# wooden_alarm.net
KiCad netlist of a schematic drawn in EAGLE
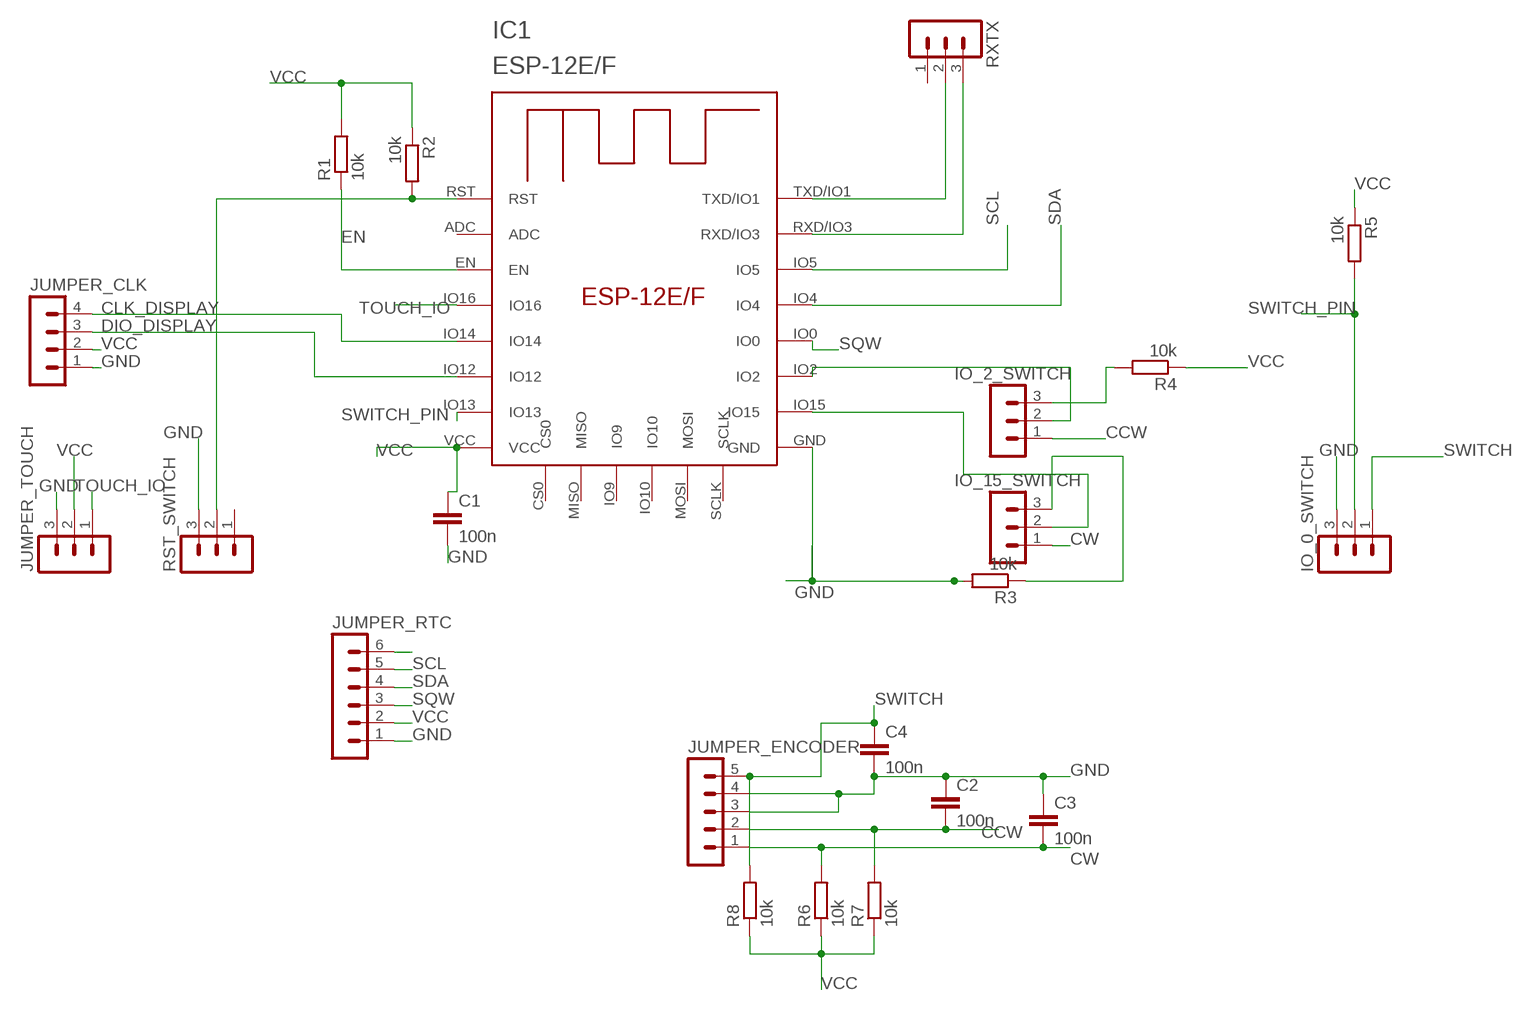
[diagram p0: schematic, sheet 1]

(export (version "E")
  (design (tool "Eeschema 10.0.6"))
  (components
    (comp (ref "C1")
      (value "100n")
      (footprint "eagle-import:C0805")
      (libsource (lib "eagle-import") (part "C-EUC0805"))
    )
    (comp (ref "C2")
      (value "100n")
      (footprint "eagle-import:C1206")
      (libsource (lib "eagle-import") (part "C-EUC1206"))
    )
    (comp (ref "C3")
      (value "100n")
      (footprint "eagle-import:C1206")
      (libsource (lib "eagle-import") (part "C-EUC1206"))
    )
    (comp (ref "C4")
      (value "100n")
      (footprint "eagle-import:C1206")
      (libsource (lib "eagle-import") (part "C-EUC1206"))
    )
    (comp (ref "IC1")
      (value "ESP-12E/F")
      (footprint "eagle-import:ESP-12E")
      (libsource (lib "eagle-import") (part "ESP-12E/F"))
    )
    (comp (ref "IO_0_SWITCH")
      (value "MA03-1")
      (footprint "eagle-import:MA03-1")
      (libsource (lib "eagle-import") (part "MA03-1"))
    )
    (comp (ref "IO_2_SWITCH")
      (value "MA03-1")
      (footprint "eagle-import:MA03-1")
      (libsource (lib "eagle-import") (part "MA03-1"))
    )
    (comp (ref "IO_15_SWITCH")
      (value "MA03-1")
      (footprint "eagle-import:MA03-1")
      (libsource (lib "eagle-import") (part "MA03-1"))
    )
    (comp (ref "JUMPER_CLK")
      (value "MA04-1")
      (footprint "eagle-import:MA04-1")
      (libsource (lib "eagle-import") (part "MA04-1"))
    )
    (comp (ref "JUMPER_ENCODER")
      (value "MA05-1")
      (footprint "eagle-import:MA05-1")
      (libsource (lib "eagle-import") (part "MA05-1"))
    )
    (comp (ref "JUMPER_RTC")
      (value "MA06-1")
      (footprint "eagle-import:MA06-1")
      (libsource (lib "eagle-import") (part "MA06-1"))
    )
    (comp (ref "JUMPER_TOUCH")
      (value "MA03-1")
      (footprint "eagle-import:MA03-1")
      (libsource (lib "eagle-import") (part "MA03-1"))
    )
    (comp (ref "R1")
      (value "10k")
      (footprint "eagle-import:R0805")
      (libsource (lib "eagle-import") (part "R-EU_R0805"))
    )
    (comp (ref "R2")
      (value "10k")
      (footprint "eagle-import:R0805")
      (libsource (lib "eagle-import") (part "R-EU_R0805"))
    )
    (comp (ref "R3")
      (value "10k")
      (footprint "eagle-import:R0805")
      (libsource (lib "eagle-import") (part "R-EU_R0805"))
    )
    (comp (ref "R4")
      (value "10k")
      (footprint "eagle-import:R0805")
      (libsource (lib "eagle-import") (part "R-EU_R0805"))
    )
    (comp (ref "R5")
      (value "10k")
      (footprint "eagle-import:R0805")
      (libsource (lib "eagle-import") (part "R-EU_R0805"))
    )
    (comp (ref "R6")
      (value "10k")
      (footprint "eagle-import:R0805")
      (libsource (lib "eagle-import") (part "R-EU_R0805"))
    )
    (comp (ref "R7")
      (value "10k")
      (footprint "eagle-import:R0805")
      (libsource (lib "eagle-import") (part "R-EU_R0805"))
    )
    (comp (ref "R8")
      (value "10k")
      (footprint "eagle-import:R0805")
      (libsource (lib "eagle-import") (part "R-EU_R0805"))
    )
    (comp (ref "RST_SWITCH")
      (value "MA03-1")
      (footprint "eagle-import:MA03-1")
      (libsource (lib "eagle-import") (part "MA03-1"))
    )
    (comp (ref "RXTX")
      (value "MA03-1")
      (footprint "eagle-import:MA03-1")
      (libsource (lib "eagle-import") (part "MA03-1"))
    )
  )
  (nets
    (net (code "1") (name "/CCW") (class "Default")
      (node (ref "C2") (pin "2") (pinfunction "2_2") (pintype "passive"))
      (node (ref "IO_2_SWITCH") (pin "1") (pinfunction "1_1") (pintype "passive"))
      (node (ref "JUMPER_ENCODER") (pin "2") (pinfunction "2_2") (pintype "passive"))
      (node (ref "R7") (pin "2") (pinfunction "2_2") (pintype "passive"))
    )
    (net (code "2") (name "/CLK_DISPLAY") (class "Default")
      (node (ref "IC1") (pin "IO14") (pinfunction "IO14_IO14") (pintype "bidirectional"))
      (node (ref "JUMPER_CLK") (pin "4") (pinfunction "4_4") (pintype "passive"))
    )
    (net (code "3") (name "/CW") (class "Default")
      (node (ref "C3") (pin "2") (pinfunction "2_2") (pintype "passive"))
      (node (ref "IO_15_SWITCH") (pin "1") (pinfunction "1_1") (pintype "passive"))
      (node (ref "JUMPER_ENCODER") (pin "1") (pinfunction "1_1") (pintype "passive"))
      (node (ref "R6") (pin "2") (pinfunction "2_2") (pintype "passive"))
    )
    (net (code "4") (name "/DIO_DISPLAY") (class "Default")
      (node (ref "IC1") (pin "IO12") (pinfunction "IO12_IO12") (pintype "bidirectional"))
      (node (ref "JUMPER_CLK") (pin "3") (pinfunction "3_3") (pintype "passive"))
    )
    (net (code "5") (name "/EN") (class "Default")
      (node (ref "IC1") (pin "EN") (pinfunction "EN_EN") (pintype "bidirectional"))
      (node (ref "R1") (pin "1") (pinfunction "1_1") (pintype "passive"))
    )
    (net (code "6") (name "/GND") (class "Default")
      (node (ref "C1") (pin "2") (pinfunction "2_2") (pintype "passive"))
      (node (ref "C2") (pin "1") (pinfunction "1_1") (pintype "passive"))
      (node (ref "C3") (pin "1") (pinfunction "1_1") (pintype "passive"))
      (node (ref "C4") (pin "2") (pinfunction "2_2") (pintype "passive"))
      (node (ref "IC1") (pin "GND") (pinfunction "GND_GND") (pintype "power_in"))
      (node (ref "IO_0_SWITCH") (pin "3") (pinfunction "3_3") (pintype "passive"))
      (node (ref "JUMPER_CLK") (pin "1") (pinfunction "1_1") (pintype "passive"))
      (node (ref "JUMPER_ENCODER") (pin "3") (pinfunction "3_3") (pintype "passive"))
      (node (ref "JUMPER_ENCODER") (pin "4") (pinfunction "4_4") (pintype "passive"))
      (node (ref "JUMPER_RTC") (pin "1") (pinfunction "1_1") (pintype "passive"))
      (node (ref "JUMPER_TOUCH") (pin "3") (pinfunction "3_3") (pintype "passive"))
      (node (ref "R3") (pin "2") (pinfunction "2_2") (pintype "passive"))
      (node (ref "RST_SWITCH") (pin "3") (pinfunction "3_3") (pintype "passive"))
    )
    (net (code "7") (name "/SCL") (class "Default")
      (node (ref "IC1") (pin "IO5") (pinfunction "IO5_IO5") (pintype "bidirectional"))
      (node (ref "JUMPER_RTC") (pin "5") (pinfunction "5_5") (pintype "passive"))
    )
    (net (code "8") (name "/SDA") (class "Default")
      (node (ref "IC1") (pin "IO4") (pinfunction "IO4_IO4") (pintype "bidirectional"))
      (node (ref "JUMPER_RTC") (pin "4") (pinfunction "4_4") (pintype "passive"))
    )
    (net (code "9") (name "/SQW") (class "Default")
      (node (ref "IC1") (pin "IO0") (pinfunction "IO0_IO0") (pintype "bidirectional"))
      (node (ref "JUMPER_RTC") (pin "3") (pinfunction "3_3") (pintype "passive"))
    )
    (net (code "10") (name "/SWITCH") (class "Default")
      (node (ref "C4") (pin "1") (pinfunction "1_1") (pintype "passive"))
      (node (ref "IO_0_SWITCH") (pin "1") (pinfunction "1_1") (pintype "passive"))
      (node (ref "JUMPER_ENCODER") (pin "5") (pinfunction "5_5") (pintype "passive"))
      (node (ref "R8") (pin "2") (pinfunction "2_2") (pintype "passive"))
    )
    (net (code "11") (name "/SWITCH_PIN") (class "Default")
      (node (ref "IC1") (pin "IO13") (pinfunction "IO13_IO13") (pintype "bidirectional"))
      (node (ref "IO_0_SWITCH") (pin "2") (pinfunction "2_2") (pintype "passive"))
      (node (ref "R5") (pin "2") (pinfunction "2_2") (pintype "passive"))
    )
    (net (code "12") (name "/TOUCH_IO") (class "Default")
      (node (ref "IC1") (pin "IO16") (pinfunction "IO16_IO16") (pintype "bidirectional"))
      (node (ref "JUMPER_TOUCH") (pin "1") (pinfunction "1_1") (pintype "passive"))
    )
    (net (code "13") (name "/VCC") (class "Default")
      (node (ref "C1") (pin "1") (pinfunction "1_1") (pintype "passive"))
      (node (ref "IC1") (pin "VCC") (pinfunction "VCC_VCC") (pintype "power_in"))
      (node (ref "JUMPER_CLK") (pin "2") (pinfunction "2_2") (pintype "passive"))
      (node (ref "JUMPER_RTC") (pin "2") (pinfunction "2_2") (pintype "passive"))
      (node (ref "JUMPER_TOUCH") (pin "2") (pinfunction "2_2") (pintype "passive"))
      (node (ref "R1") (pin "2") (pinfunction "2_2") (pintype "passive"))
      (node (ref "R2") (pin "1") (pinfunction "1_1") (pintype "passive"))
      (node (ref "R4") (pin "1") (pinfunction "1_1") (pintype "passive"))
      (node (ref "R5") (pin "1") (pinfunction "1_1") (pintype "passive"))
      (node (ref "R6") (pin "1") (pinfunction "1_1") (pintype "passive"))
      (node (ref "R7") (pin "1") (pinfunction "1_1") (pintype "passive"))
      (node (ref "R8") (pin "1") (pinfunction "1_1") (pintype "passive"))
    )
    (net (code "14") (name "Net-(IC1-PadIO2)") (class "Default")
      (node (ref "IC1") (pin "IO2") (pinfunction "IO2_IO2") (pintype "bidirectional"))
      (node (ref "IO_2_SWITCH") (pin "2") (pinfunction "2_2") (pintype "passive"))
    )
    (net (code "15") (name "Net-(IC1-PadIO15)") (class "Default")
      (node (ref "IC1") (pin "IO15") (pinfunction "IO15_IO15") (pintype "bidirectional"))
      (node (ref "IO_15_SWITCH") (pin "2") (pinfunction "2_2") (pintype "passive"))
    )
    (net (code "16") (name "Net-(IC1-PadRST)") (class "Default")
      (node (ref "IC1") (pin "RST") (pinfunction "RST_RST") (pintype "input"))
      (node (ref "R2") (pin "2") (pinfunction "2_2") (pintype "passive"))
      (node (ref "RST_SWITCH") (pin "2") (pinfunction "2_2") (pintype "passive"))
    )
    (net (code "17") (name "Net-(IC1-PadRXD{slash}IO3)") (class "Default")
      (node (ref "IC1") (pin "RXD/IO3") (pinfunction "RXD/IO3_RXD/IO3") (pintype "bidirectional"))
      (node (ref "RXTX") (pin "3") (pinfunction "3_3") (pintype "passive"))
    )
    (net (code "18") (name "Net-(IC1-PadTXD{slash}IO1)") (class "Default")
      (node (ref "IC1") (pin "TXD/IO1") (pinfunction "TXD/IO1_TXD/IO1") (pintype "bidirectional"))
      (node (ref "RXTX") (pin "2") (pinfunction "2_2") (pintype "passive"))
    )
    (net (code "19") (name "Net-(IO_2_SWITCH-Pad3)") (class "Default")
      (node (ref "IO_2_SWITCH") (pin "3") (pinfunction "3_3") (pintype "passive"))
      (node (ref "R4") (pin "2") (pinfunction "2_2") (pintype "passive"))
    )
    (net (code "20") (name "Net-(IO_15_SWITCH-Pad3)") (class "Default")
      (node (ref "IO_15_SWITCH") (pin "3") (pinfunction "3_3") (pintype "passive"))
      (node (ref "R3") (pin "1") (pinfunction "1_1") (pintype "passive"))
    )
    (net (code "21") (name "unconnected-(IC1-PadADC)") (class "Default")
      (node (ref "IC1") (pin "ADC") (pinfunction "ADC_ADC") (pintype "bidirectional"))
    )
    (net (code "22") (name "unconnected-(IC1-PadCS0)") (class "Default")
      (node (ref "IC1") (pin "CS0") (pinfunction "CS0_CS0") (pintype "bidirectional"))
    )
    (net (code "23") (name "unconnected-(IC1-PadIO9)") (class "Default")
      (node (ref "IC1") (pin "IO9") (pinfunction "IO9_IO9") (pintype "bidirectional"))
    )
    (net (code "24") (name "unconnected-(IC1-PadIO10)") (class "Default")
      (node (ref "IC1") (pin "IO10") (pinfunction "IO10_IO10") (pintype "bidirectional"))
    )
    (net (code "25") (name "unconnected-(IC1-PadMISO)") (class "Default")
      (node (ref "IC1") (pin "MISO") (pinfunction "MISO_MISO") (pintype "bidirectional"))
    )
    (net (code "26") (name "unconnected-(IC1-PadMOSI)") (class "Default")
      (node (ref "IC1") (pin "MOSI") (pinfunction "MOSI_MOSI") (pintype "bidirectional"))
    )
    (net (code "27") (name "unconnected-(IC1-PadSCLK)") (class "Default")
      (node (ref "IC1") (pin "SCLK") (pinfunction "SCLK_SCLK") (pintype "bidirectional"))
    )
    (net (code "28") (name "unconnected-(JUMPER_RTC-Pad6)") (class "Default")
      (node (ref "JUMPER_RTC") (pin "6") (pinfunction "6_6") (pintype "passive"))
    )
    (net (code "29") (name "unconnected-(RST_SWITCH-Pad1)") (class "Default")
      (node (ref "RST_SWITCH") (pin "1") (pinfunction "1_1") (pintype "passive"))
    )
    (net (code "30") (name "unconnected-(RXTX-Pad1)") (class "Default")
      (node (ref "RXTX") (pin "1") (pinfunction "1_1") (pintype "passive"))
    )
  )
)
